# example.net
KiCad netlist of a schematic drawn in EAGLE
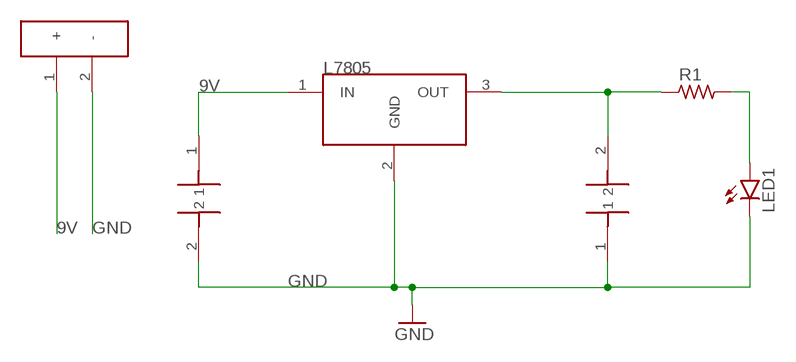
[diagram p0: schematic, sheet 1]

(export (version "E")
  (design (tool "Eeschema 10.0.6"))
  (components
    (comp (ref "LED1")
      (value "LEDCHIP-LED0805")
      (footprint "eagle-import:CHIP-LED0805")
      (libsource (lib "eagle-import") (part "LEDCHIP-LED0805"))
    )
    (comp (ref "R1")
      (value "R_1206")
      (footprint "eagle-import:R1206")
      (libsource (lib "eagle-import") (part "R_1206"))
    )
    (comp (ref "U$1")
      (value "L7805A")
      (footprint "eagle-import:L7805")
      (libsource (lib "eagle-import") (part "L7805A"))
    )
    (comp (ref "U$2")
      (value "2X1KLAMENSA")
      (footprint "eagle-import:2X1KLAMENS")
      (libsource (lib "eagle-import") (part "2X1KLAMENSA"))
    )
    (comp (ref "U$3")
      (value "0.1UF")
      (footprint "eagle-import:C1206")
      (libsource (lib "eagle-import") (part "0.1UF"))
    )
    (comp (ref "U$4")
      (value "0.33UF")
      (footprint "eagle-import:C1206")
      (libsource (lib "eagle-import") (part "0.33UF"))
    )
  )
  (nets
    (net (code "1") (name "/9V") (class "Default")
      (node (ref "U$1") (pin "1") (pinfunction "IN_1") (pintype "bidirectional"))
      (node (ref "U$2") (pin "1") (pinfunction "+_1") (pintype "bidirectional"))
      (node (ref "U$3") (pin "1") (pinfunction "1_1") (pintype "bidirectional"))
    )
    (net (code "2") (name "GND") (class "Default")
      (node (ref "LED1") (pin "C") (pinfunction "C_C") (pintype "passive"))
      (node (ref "U$1") (pin "2") (pinfunction "GND_2") (pintype "bidirectional"))
      (node (ref "U$2") (pin "2") (pinfunction "-_2") (pintype "bidirectional"))
      (node (ref "U$3") (pin "2") (pinfunction "2_2") (pintype "bidirectional"))
      (node (ref "U$4") (pin "1") (pinfunction "1_1") (pintype "bidirectional"))
    )
    (net (code "3") (name "Net-(LED1-PadA)") (class "Default")
      (node (ref "LED1") (pin "A") (pinfunction "A_A") (pintype "passive"))
      (node (ref "R1") (pin "2") (pinfunction "2_2") (pintype "passive"))
    )
    (net (code "4") (name "Net-(U$1-OUT)") (class "Default")
      (node (ref "R1") (pin "1") (pinfunction "1_1") (pintype "passive"))
      (node (ref "U$1") (pin "3") (pinfunction "OUT_3") (pintype "bidirectional"))
      (node (ref "U$4") (pin "2") (pinfunction "2_2") (pintype "bidirectional"))
    )
  )
)
